# RPL_POWER_SOLENOIDS.net
KiCad netlist of a schematic drawn in Altium Designer
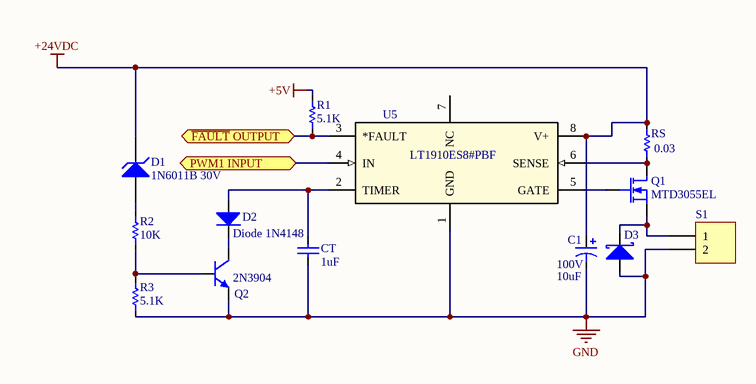
[diagram p0: RPL_POWER_SOLENOIDS.SchDoc]

(export (version "E")
  (design (tool "Eeschema 10.0.6"))
  (components
    (comp (ref "C1")
      (value "100V")
      (footprint "CAPAE430X550N:RADIAL")
      (fields (field (name "ALTIUM_VALUE") "10uF"))
      (libsource (lib "Generic_Library") (part "Cap Elec"))
    )
    (comp (ref "CT")
      (value "1uF")
      (footprint "C0402T104K4RACTU")
      (fields (field (name "Comment") "Cap"))
      (libsource (lib "Generic_Library") (part "Cap"))
    )
    (comp (ref "D1")
      (value "1N6011B 30V")
      (footprint "DIODE-0.7")
      (description "Zener Diode")
      (fields (field (name "PUBLISHER") "Altium Limited"))
      (libsource (lib "Generic_Library") (part "D Zener"))
    )
    (comp (ref "D2")
      (value "Diode 1N4148")
      (footprint "DO-35")
      (description "High Conductance Fast Diode")
      (fields (field (name "PUBLISHER") "Altium Limited"))
      (libsource (lib "Generic_Library") (part "Diode 1N4148"))
    )
    (comp (ref "D3")
      (value "Diod")
      (footprint "SOD323_F_:SOD323_F")
      (libsource (lib "Generic_Library") (part "Diod"))
    )
    (comp (ref "Q1")
      (value "MTD3055EL")
      (footprint "TO229P990X239-3N")
      (libsource (lib "Generic_Library") (part "Mosfet"))
    )
    (comp (ref "Q2")
      (value "2N3904")
      (footprint "TO-92A")
      (description "NPN General Purpose Amplifier")
      (fields (field (name "PUBLISHER") "Altium Limited"))
      (libsource (lib "Generic_Library") (part "2N3904"))
    )
    (comp (ref "R1")
      (value "5.1K")
      (footprint "RC0603JR-070RL:0603")
      (fields (field (name "Comment") "Res"))
      (libsource (lib "Generic_Library") (part "Res"))
    )
    (comp (ref "R2")
      (value "10K")
      (footprint "RC0603JR-070RL:0603")
      (fields (field (name "Comment") "Res"))
      (libsource (lib "Generic_Library") (part "Res"))
    )
    (comp (ref "R3")
      (value "5.1K")
      (footprint "RC0603JR-070RL:0603")
      (fields (field (name "Comment") "Res"))
      (libsource (lib "Generic_Library") (part "Res"))
    )
    (comp (ref "RS")
      (value "0.03")
      (footprint "RC0603JR-070RL:0603")
      (fields (field (name "Comment") "Res"))
      (libsource (lib "Generic_Library") (part "Res"))
    )
    (comp (ref "S1")
      (value "Header 2")
      (footprint "HDR1X2")
      (description "Header, 2-Pin")
      (fields (field (name "PUBLISHER") "Altium Limited"))
      (libsource (lib "Miscellaneous Connectors") (part "Header 2"))
    )
    (comp (ref "U5")
      (value "LT1910ES8#PBF")
      (footprint "LT1910:SO-8_S")
      (description "Imported")
      (fields (field (name "MANUFACTURER_PART_NUMBER") "lt1910es8#pbf"))
      (libsource (lib "Generic_Library") (part "LT1910ES8#PBF"))
    )
  )
  (nets
    (net (code "1") (name "+5V") (class "Default")
      (node (ref "R1") (pin "2") (pinfunction "2_2") (pintype "passive"))
    )
    (net (code "2") (name "+24VDC") (class "Default")
      (node (ref "C1") (pin "1") (pinfunction "1_1") (pintype "passive"))
      (node (ref "D1") (pin "2") (pinfunction "K_2") (pintype "passive"))
      (node (ref "RS") (pin "2") (pinfunction "2_2") (pintype "passive"))
      (node (ref "U5") (pin "8") (pinfunction "V+_8") (pintype "power_in"))
    )
    (net (code "3") (name "/PWM1 INPUT") (class "Default")
      (node (ref "U5") (pin "4") (pinfunction "IN_4") (pintype "input"))
    )
    (net (code "4") (name "/~{FAULT} OUTPUT") (class "Default")
      (node (ref "R1") (pin "1") (pinfunction "1_1") (pintype "passive"))
      (node (ref "U5") (pin "3") (pinfunction "*FAULT_3") (pintype "passive"))
    )
    (net (code "5") (name "GND") (class "Default")
      (node (ref "C1") (pin "2") (pinfunction "2_2") (pintype "passive"))
      (node (ref "CT") (pin "1") (pinfunction "1_1") (pintype "passive"))
      (node (ref "D3") (pin "1") (pinfunction "A_1") (pintype "passive"))
      (node (ref "Q2") (pin "1") (pinfunction "E_1") (pintype "passive"))
      (node (ref "R3") (pin "1") (pinfunction "1_1") (pintype "passive"))
      (node (ref "S1") (pin "2") (pinfunction "2_2") (pintype "passive"))
      (node (ref "U5") (pin "1") (pinfunction "GND_1") (pintype "power_in"))
    )
    (net (code "6") (name "Net-(D1-A)") (class "Default")
      (node (ref "D1") (pin "1") (pinfunction "A_1") (pintype "passive"))
      (node (ref "R2") (pin "2") (pinfunction "2_2") (pintype "passive"))
    )
    (net (code "7") (name "Net-(D2-A)") (class "Default")
      (node (ref "CT") (pin "2") (pinfunction "2_2") (pintype "passive"))
      (node (ref "D2") (pin "1") (pinfunction "A_1") (pintype "passive"))
      (node (ref "U5") (pin "2") (pinfunction "TIMER_2") (pintype "passive"))
    )
    (net (code "8") (name "Net-(D2-K)") (class "Default")
      (node (ref "D2") (pin "2") (pinfunction "K_2") (pintype "passive"))
      (node (ref "Q2") (pin "3") (pinfunction "C_3") (pintype "passive"))
    )
    (net (code "9") (name "Net-(D3-K)") (class "Default")
      (node (ref "D3") (pin "3") (pinfunction "K_3") (pintype "passive"))
      (node (ref "Q1") (pin "3") (pinfunction "S_3") (pintype "passive"))
      (node (ref "S1") (pin "1") (pinfunction "1_1") (pintype "passive"))
    )
    (net (code "10") (name "Net-(Q1-D)") (class "Default")
      (node (ref "Q1") (pin "1") (pinfunction "D_1") (pintype "passive"))
      (node (ref "RS") (pin "1") (pinfunction "1_1") (pintype "passive"))
      (node (ref "U5") (pin "6") (pinfunction "SENSE_6") (pintype "input"))
    )
    (net (code "11") (name "Net-(Q1-G)") (class "Default")
      (node (ref "Q1") (pin "2") (pinfunction "G_2") (pintype "passive"))
      (node (ref "U5") (pin "5") (pinfunction "GATE_5") (pintype "passive"))
    )
    (net (code "12") (name "Net-(Q2-B)") (class "Default")
      (node (ref "Q2") (pin "2") (pinfunction "B_2") (pintype "passive"))
      (node (ref "R2") (pin "1") (pinfunction "1_1") (pintype "passive"))
      (node (ref "R3") (pin "2") (pinfunction "2_2") (pintype "passive"))
    )
    (net (code "13") (name "unconnected-(U5-NC-Pad7)") (class "Default")
      (node (ref "U5") (pin "7") (pinfunction "NC_7") (pintype "passive"))
    )
  )
)
